# Accelerometer.net
KiCad netlist of a schematic drawn in Altium Designer
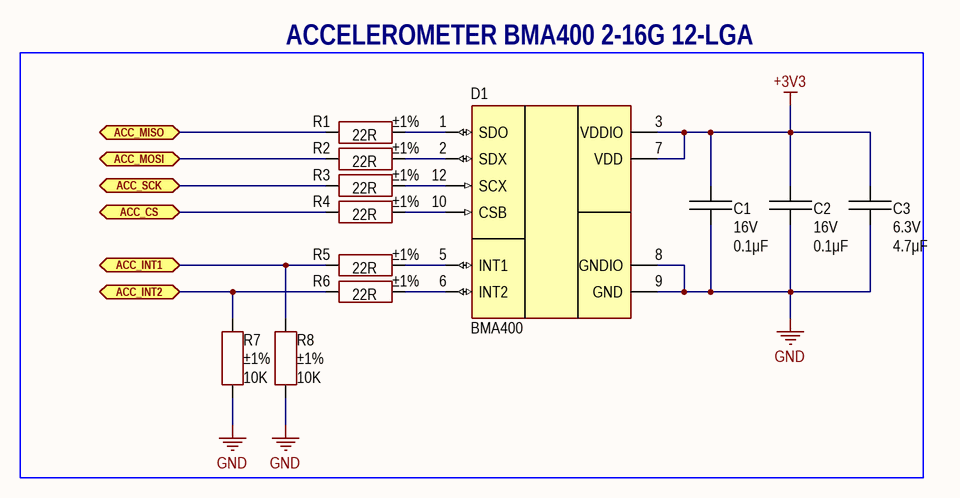
[diagram p0: Accelerometer.SchDoc]

(export (version "E")
  (design (tool "Eeschema 10.0.6"))
  (components
    (comp (ref "C1")
      (value "0.1μF")
      (footprint "CAP: 0402_NO_SILK")
      (description "0.1 µF ±10% 16V Ceramic Capacitor X7R 0402 (1005 Metric)")
      (fields
        (field (name "MANUFACTURER") "Yageo")
        (field (name "PARTNUMBER") "CC0402KRX7R7BB104")
        (field (name "VOLTAGE") "16V")
      )
      (libsource (lib "capacitor") (part "Ceramic_0402"))
    )
    (comp (ref "C2")
      (value "0.1μF")
      (footprint "CAP: 0402_NO_SILK")
      (description "0.1 µF ±10% 16V Ceramic Capacitor X7R 0402 (1005 Metric)")
      (fields
        (field (name "MANUFACTURER") "Yageo")
        (field (name "PARTNUMBER") "CC0402KRX7R7BB104")
        (field (name "VOLTAGE") "16V")
      )
      (libsource (lib "capacitor") (part "Ceramic_0402"))
    )
    (comp (ref "C3")
      (value "4.7μF")
      (footprint "CAP: 0603_NO_SILK")
      (description "4.7 µF ±20% 6.3V Ceramic Capacitor X7R 0603 (1608 Metric)")
      (fields
        (field (name "MANUFACTURER") "Yageo")
        (field (name "PARTNUMBER") "CC0603MRX7R5BB475")
        (field (name "VOLTAGE") "6.3V")
      )
      (libsource (lib "capacitor") (part "Ceramic_0603"))
    )
    (comp (ref "D1")
      (value "~")
      (footprint "12-VFLGA")
      (description "Accelerometer")
      (fields
        (field (name "MANUFACTURER") "Bosch Sensortec")
        (field (name "VALUEMANUFACTURERPARTNUMBER") "IC accelerometer, Digital sensor, , , , -40...+85°C, 12-VFLGA")
        (field (name "PARTNUMBER") "BMA400")
      )
      (libsource (lib "MyLib") (part "BMA400"))
    )
    (comp (ref "R1")
      (value "22R")
      (footprint "RES: 0201")
      (description "22 Ohms ±1% 0.05W, 1/20W Chip Resistor 0201 (0603 Metric) Moisture Resistant Thick Film")
      (fields
        (field (name "MANUFACTURER") "Yageo")
        (field (name "PARTNUMBER") "RC0201FR-0722RL")
        (field (name "TOLERANCE") "±1%")
      )
      (libsource (lib "resistor") (part "Resistor_0201"))
    )
    (comp (ref "R2")
      (value "22R")
      (footprint "RES: 0201")
      (description "22 Ohms ±1% 0.05W, 1/20W Chip Resistor 0201 (0603 Metric) Moisture Resistant Thick Film")
      (fields
        (field (name "MANUFACTURER") "Yageo")
        (field (name "PARTNUMBER") "RC0201FR-0722RL")
        (field (name "TOLERANCE") "±1%")
      )
      (libsource (lib "resistor") (part "Resistor_0201"))
    )
    (comp (ref "R3")
      (value "22R")
      (footprint "RES: 0201")
      (description "22 Ohms ±1% 0.05W, 1/20W Chip Resistor 0201 (0603 Metric) Moisture Resistant Thick Film")
      (fields
        (field (name "MANUFACTURER") "Yageo")
        (field (name "PARTNUMBER") "RC0201FR-0722RL")
        (field (name "TOLERANCE") "±1%")
      )
      (libsource (lib "resistor") (part "Resistor_0201"))
    )
    (comp (ref "R4")
      (value "22R")
      (footprint "RES: 0201")
      (description "22 Ohms ±1% 0.05W, 1/20W Chip Resistor 0201 (0603 Metric) Moisture Resistant Thick Film")
      (fields
        (field (name "MANUFACTURER") "Yageo")
        (field (name "PARTNUMBER") "RC0201FR-0722RL")
        (field (name "TOLERANCE") "±1%")
      )
      (libsource (lib "resistor") (part "Resistor_0201"))
    )
    (comp (ref "R5")
      (value "22R")
      (footprint "RES: 0201")
      (description "22 Ohms ±1% 0.05W, 1/20W Chip Resistor 0201 (0603 Metric) Moisture Resistant Thick Film")
      (fields
        (field (name "MANUFACTURER") "Yageo")
        (field (name "PARTNUMBER") "RC0201FR-0722RL")
        (field (name "TOLERANCE") "±1%")
      )
      (libsource (lib "resistor") (part "Resistor_0201"))
    )
    (comp (ref "R6")
      (value "22R")
      (footprint "RES: 0201")
      (description "22 Ohms ±1% 0.05W, 1/20W Chip Resistor 0201 (0603 Metric) Moisture Resistant Thick Film")
      (fields
        (field (name "MANUFACTURER") "Yageo")
        (field (name "PARTNUMBER") "RC0201FR-0722RL")
        (field (name "TOLERANCE") "±1%")
      )
      (libsource (lib "resistor") (part "Resistor_0201"))
    )
    (comp (ref "R7")
      (value "10K")
      (footprint "RES: 0201")
      (description "10 kOhms ±1% 0.05W, 1/20W Chip Resistor 0201 (0603 Metric) Moisture Resistant Thick Film")
      (fields
        (field (name "MANUFACTURER") "Yageo")
        (field (name "PARTNUMBER") "RC0201JR-0710KL")
        (field (name "TOLERANCE") "±1%")
      )
      (libsource (lib "") (part "Resistor_0201_1"))
    )
    (comp (ref "R8")
      (value "10K")
      (footprint "RES: 0201")
      (description "10 kOhms ±1% 0.05W, 1/20W Chip Resistor 0201 (0603 Metric) Moisture Resistant Thick Film")
      (fields
        (field (name "MANUFACTURER") "Yageo")
        (field (name "PARTNUMBER") "RC0201JR-0710KL")
        (field (name "TOLERANCE") "±1%")
      )
      (libsource (lib "") (part "Resistor_0201_1"))
    )
  )
  (nets
    (net (code "1") (name "+3V3") (class "Default")
      (node (ref "C1") (pin "2") (pinfunction "2_2") (pintype "passive"))
      (node (ref "C2") (pin "2") (pinfunction "2_2") (pintype "passive"))
      (node (ref "C3") (pin "2") (pinfunction "2_2") (pintype "passive"))
      (node (ref "D1") (pin "3") (pinfunction "VDDIO_3") (pintype "power_in"))
      (node (ref "D1") (pin "7") (pinfunction "VDD_7") (pintype "power_in"))
    )
    (net (code "2") (name "/ACC_CS") (class "Default")
      (node (ref "R4") (pin "2") (pinfunction "2_2") (pintype "passive"))
    )
    (net (code "3") (name "/ACC_INT1") (class "Default")
      (node (ref "R5") (pin "2") (pinfunction "2_2") (pintype "passive"))
      (node (ref "R8") (pin "2") (pinfunction "2_2") (pintype "passive"))
    )
    (net (code "4") (name "/ACC_INT2") (class "Default")
      (node (ref "R6") (pin "2") (pinfunction "2_2") (pintype "passive"))
      (node (ref "R7") (pin "2") (pinfunction "2_2") (pintype "passive"))
    )
    (net (code "5") (name "/ACC_MISO") (class "Default")
      (node (ref "R1") (pin "2") (pinfunction "2_2") (pintype "passive"))
    )
    (net (code "6") (name "/ACC_MOSI") (class "Default")
      (node (ref "R2") (pin "2") (pinfunction "2_2") (pintype "passive"))
    )
    (net (code "7") (name "/ACC_SCK") (class "Default")
      (node (ref "R3") (pin "2") (pinfunction "2_2") (pintype "passive"))
    )
    (net (code "8") (name "GND") (class "Default")
      (node (ref "C1") (pin "1") (pinfunction "1_1") (pintype "passive"))
      (node (ref "C2") (pin "1") (pinfunction "1_1") (pintype "passive"))
      (node (ref "C3") (pin "1") (pinfunction "1_1") (pintype "passive"))
      (node (ref "D1") (pin "8") (pinfunction "GNDIO_8") (pintype "power_in"))
      (node (ref "D1") (pin "9") (pinfunction "GND_9") (pintype "power_in"))
      (node (ref "R7") (pin "1") (pinfunction "1_1") (pintype "passive"))
      (node (ref "R8") (pin "1") (pinfunction "1_1") (pintype "passive"))
    )
    (net (code "9") (name "Net-(D1-CSB)") (class "Default")
      (node (ref "D1") (pin "10") (pinfunction "CSB_10") (pintype "input"))
      (node (ref "R4") (pin "1") (pinfunction "1_1") (pintype "passive"))
    )
    (net (code "10") (name "Net-(D1-INT1)") (class "Default")
      (node (ref "D1") (pin "5") (pinfunction "INT1_5") (pintype "bidirectional"))
      (node (ref "R5") (pin "1") (pinfunction "1_1") (pintype "passive"))
    )
    (net (code "11") (name "Net-(D1-INT2)") (class "Default")
      (node (ref "D1") (pin "6") (pinfunction "INT2_6") (pintype "bidirectional"))
      (node (ref "R6") (pin "1") (pinfunction "1_1") (pintype "passive"))
    )
    (net (code "12") (name "Net-(D1-SCX)") (class "Default")
      (node (ref "D1") (pin "12") (pinfunction "SCX_12") (pintype "input"))
      (node (ref "R3") (pin "1") (pinfunction "1_1") (pintype "passive"))
    )
    (net (code "13") (name "Net-(D1-SDO)") (class "Default")
      (node (ref "D1") (pin "1") (pinfunction "SDO_1") (pintype "bidirectional"))
      (node (ref "R1") (pin "1") (pinfunction "1_1") (pintype "passive"))
    )
    (net (code "14") (name "Net-(D1-SDX)") (class "Default")
      (node (ref "D1") (pin "2") (pinfunction "SDX_2") (pintype "bidirectional"))
      (node (ref "R2") (pin "1") (pinfunction "1_1") (pintype "passive"))
    )
  )
)
